# hexapod_mk2_leg_v0_0.net
KiCad netlist of a schematic drawn in EAGLE
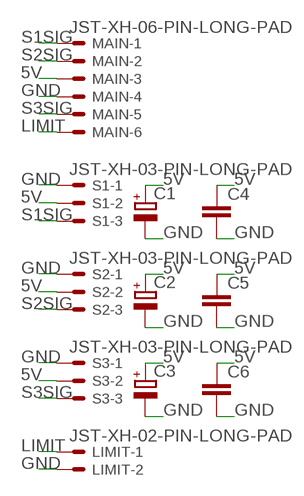
[diagram p0: schematic, sheet 1]

(export (version "E")
  (design (tool "Eeschema 10.0.6"))
  (components
    (comp (ref "C1")
      (value "CPOL-EUE2-5")
      (footprint "eagle-import:E2-5")
      (libsource (lib "eagle-import") (part "CPOL-EUE2-5"))
    )
    (comp (ref "C2")
      (value "CPOL-EUE2-5")
      (footprint "eagle-import:E2-5")
      (libsource (lib "eagle-import") (part "CPOL-EUE2-5"))
    )
    (comp (ref "C3")
      (value "CPOL-EUE2-5")
      (footprint "eagle-import:E2-5")
      (libsource (lib "eagle-import") (part "CPOL-EUE2-5"))
    )
    (comp (ref "C4")
      (value "C-EUC1206")
      (footprint "eagle-import:C1206")
      (libsource (lib "eagle-import") (part "C-EUC1206"))
    )
    (comp (ref "C5")
      (value "C-EUC1206")
      (footprint "eagle-import:C1206")
      (libsource (lib "eagle-import") (part "C-EUC1206"))
    )
    (comp (ref "C6")
      (value "C-EUC1206")
      (footprint "eagle-import:C1206")
      (libsource (lib "eagle-import") (part "C-EUC1206"))
    )
    (comp (ref "LIMIT")
      (value "JST-XH-02-PIN-LONG-PAD")
      (footprint "eagle-import:JST-XH-02-PACKAGE-LONG-PAD")
      (libsource (lib "eagle-import") (part "JST-XH-02-PIN-LONG-PAD"))
    )
    (comp (ref "MAIN")
      (value "JST-XH-06-PIN-LONG-PAD")
      (footprint "eagle-import:JST-XH-06-PACKAGE-LONG-PAD")
      (libsource (lib "eagle-import") (part "JST-XH-06-PIN-LONG-PAD"))
    )
    (comp (ref "S1")
      (value "JST-XH-03-PIN-LONG-PAD")
      (footprint "eagle-import:JST-XH-03-PACKAGE-LONG-PAD")
      (libsource (lib "eagle-import") (part "JST-XH-03-PIN-LONG-PAD"))
    )
    (comp (ref "S2")
      (value "JST-XH-03-PIN-LONG-PAD")
      (footprint "eagle-import:JST-XH-03-PACKAGE-LONG-PAD")
      (libsource (lib "eagle-import") (part "JST-XH-03-PIN-LONG-PAD"))
    )
    (comp (ref "S3")
      (value "JST-XH-03-PIN-LONG-PAD")
      (footprint "eagle-import:JST-XH-03-PACKAGE-LONG-PAD")
      (libsource (lib "eagle-import") (part "JST-XH-03-PIN-LONG-PAD"))
    )
  )
  (nets
    (net (code "1") (name "/5V") (class "Default")
      (node (ref "C1") (pin "+") (pinfunction "+_+") (pintype "passive"))
      (node (ref "C2") (pin "+") (pinfunction "+_+") (pintype "passive"))
      (node (ref "C3") (pin "+") (pinfunction "+_+") (pintype "passive"))
      (node (ref "C4") (pin "1") (pinfunction "1_1") (pintype "passive"))
      (node (ref "C5") (pin "1") (pinfunction "1_1") (pintype "passive"))
      (node (ref "C6") (pin "1") (pinfunction "1_1") (pintype "passive"))
      (node (ref "MAIN") (pin "3") (pinfunction "S_3") (pintype "passive"))
      (node (ref "S1") (pin "2") (pinfunction "S_2") (pintype "passive"))
      (node (ref "S2") (pin "2") (pinfunction "S_2") (pintype "passive"))
      (node (ref "S3") (pin "2") (pinfunction "S_2") (pintype "passive"))
    )
    (net (code "2") (name "/GND") (class "Default")
      (node (ref "C1") (pin "-") (pinfunction "-_-") (pintype "passive"))
      (node (ref "C2") (pin "-") (pinfunction "-_-") (pintype "passive"))
      (node (ref "C3") (pin "-") (pinfunction "-_-") (pintype "passive"))
      (node (ref "C4") (pin "2") (pinfunction "2_2") (pintype "passive"))
      (node (ref "C5") (pin "2") (pinfunction "2_2") (pintype "passive"))
      (node (ref "C6") (pin "2") (pinfunction "2_2") (pintype "passive"))
      (node (ref "LIMIT") (pin "2") (pinfunction "S_2") (pintype "passive"))
      (node (ref "MAIN") (pin "4") (pinfunction "S_4") (pintype "passive"))
      (node (ref "S1") (pin "1") (pinfunction "S_1") (pintype "passive"))
      (node (ref "S2") (pin "1") (pinfunction "S_1") (pintype "passive"))
      (node (ref "S3") (pin "1") (pinfunction "S_1") (pintype "passive"))
    )
    (net (code "3") (name "/LIMIT") (class "Default")
      (node (ref "LIMIT") (pin "1") (pinfunction "S_1") (pintype "passive"))
      (node (ref "MAIN") (pin "6") (pinfunction "S_6") (pintype "passive"))
    )
    (net (code "4") (name "/S1SIG") (class "Default")
      (node (ref "MAIN") (pin "1") (pinfunction "S_1") (pintype "passive"))
      (node (ref "S1") (pin "3") (pinfunction "S_3") (pintype "passive"))
    )
    (net (code "5") (name "/S2SIG") (class "Default")
      (node (ref "MAIN") (pin "2") (pinfunction "S_2") (pintype "passive"))
      (node (ref "S2") (pin "3") (pinfunction "S_3") (pintype "passive"))
    )
    (net (code "6") (name "/S3SIG") (class "Default")
      (node (ref "MAIN") (pin "5") (pinfunction "S_5") (pintype "passive"))
      (node (ref "S3") (pin "3") (pinfunction "S_3") (pintype "passive"))
    )
  )
)
